# LCD_Interface.net
KiCad netlist of a schematic drawn in Altium Designer
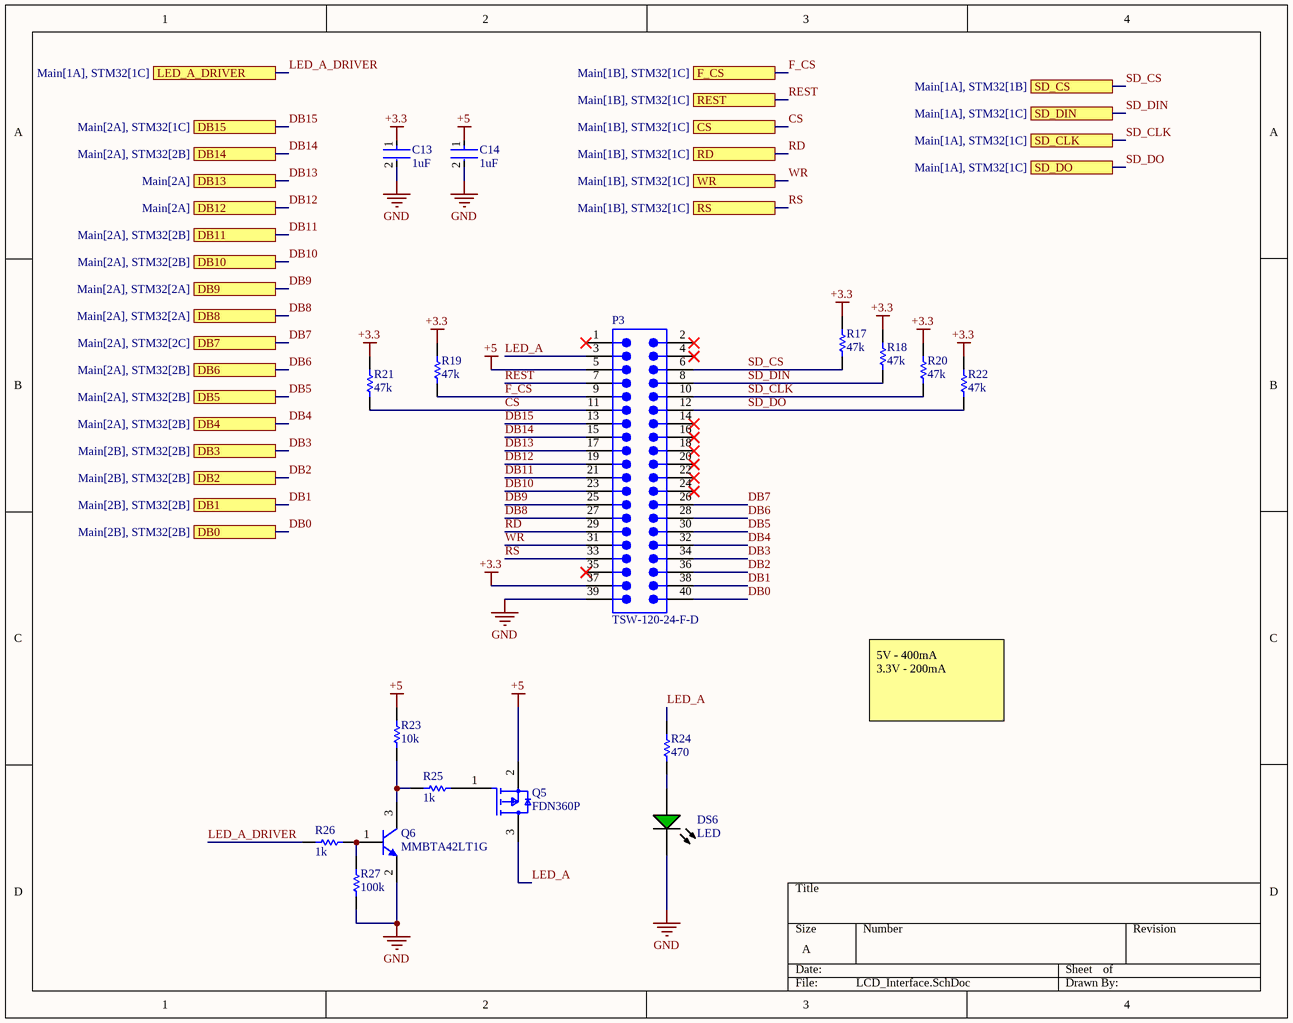
[diagram p0: LCD_Interface.SchDoc]

(export (version "E")
  (design (tool "Eeschema 10.0.6"))
  (components
    (comp (ref "C13")
      (value "1uF")
      (footprint "FP-0805-L_2_01_0_2-W_1_25-IPC_B")
      (description "General Purpose Ceramic Capacitor, 0805, 100nF, 10%, X7R, 15%, 100V")
      (fields (field (name "VOLTAGE") "100V") (field (name "TOLERANCE") "10%"))
      (libsource (lib "Altium Content Vault") (part "b4654b650e69147ec39a6b967a45e02"))
    )
    (comp (ref "C14")
      (value "1uF")
      (footprint "FP-0805-L_2_01_0_2-W_1_25-IPC_B")
      (description "General Purpose Ceramic Capacitor, 0805, 100nF, 10%, X7R, 15%, 100V")
      (fields (field (name "VOLTAGE") "100V") (field (name "TOLERANCE") "10%"))
      (libsource (lib "Altium Content Vault") (part "b4654b650e69147ec39a6b967a45e02"))
    )
    (comp (ref "DS6")
      (value "LED")
      (footprint "AVAG-HSMX-C170_V")
      (description "Chip LED, Green, 2.2 V, -40 to 85 degC, 2-Pin SMD, Pb-Free, Tape and Reel")
      (fields (field (name "MANUFACTURER") "Avago"))
      (libsource (lib "Altium Content Vault") (part "LED_GREEN_A1K2-2"))
    )
    (comp (ref "P3")
      (value "TSW-120-24-F-D")
      (footprint "SMTC-TSW-120-24-X-D")
      (description "0.025\" SQ Post Header, Through-hole, Vertical, -55 to 125 degC, 2.54 mm Pitch, 40-Pin, Male, RoHS")
      (fields (field (name "MANUFACTURER") "Samtec"))
      (libsource (lib "Altium Content Vault") (part "SMTC-TSW-120-X-X-D-X"))
    )
    (comp (ref "Q5")
      (value "FDN360P")
      (footprint "FP-527AG-IPC_B")
      (description "MOSFET P-CH 30V 2A SSOT3")
      (libsource (lib "Altium Content Vault") (part "d96140c8e79ef71348df71fb49a9466"))
    )
    (comp (ref "Q6")
      (value "MMBTA42LT1G")
      (footprint "ONSC-SOT-23-3-318-08_V")
      (description "High Voltage Transistor, NPN Silicon, 3-Pin SOT-23, Pb-Free, Tape and Reel")
      (fields (field (name "MANUFACTURER") "On Semiconductor"))
      (libsource (lib "Altium Content Vault") (part "ONSC-NPN-B1E2C3-3"))
    )
    (comp (ref "R17")
      (value "47k")
      (footprint "RESC2013X50X30LL20T20")
      (fields (field (name "MANUFACTURER") "Vishay Dale") (field (name "PART NUMBER") "CRCW08050000Z0EA"))
      (libsource (lib "Altium Content Vault") (part "RES"))
    )
    (comp (ref "R18")
      (value "47k")
      (footprint "RESC2013X50X30LL20T20")
      (fields (field (name "MANUFACTURER") "Vishay Dale") (field (name "PART NUMBER") "CRCW08050000Z0EA"))
      (libsource (lib "Altium Content Vault") (part "RES"))
    )
    (comp (ref "R19")
      (value "47k")
      (footprint "RESC2013X50X30LL20T20")
      (fields (field (name "MANUFACTURER") "Vishay Dale") (field (name "PART NUMBER") "CRCW08050000Z0EA"))
      (libsource (lib "Altium Content Vault") (part "RES"))
    )
    (comp (ref "R20")
      (value "47k")
      (footprint "RESC2013X50X30LL20T20")
      (fields (field (name "MANUFACTURER") "Vishay Dale") (field (name "PART NUMBER") "CRCW08050000Z0EA"))
      (libsource (lib "Altium Content Vault") (part "RES"))
    )
    (comp (ref "R21")
      (value "47k")
      (footprint "RESC2013X50X30LL20T20")
      (fields (field (name "MANUFACTURER") "Vishay Dale") (field (name "PART NUMBER") "CRCW08050000Z0EA"))
      (libsource (lib "Altium Content Vault") (part "RES"))
    )
    (comp (ref "R22")
      (value "47k")
      (footprint "RESC2013X50X30LL20T20")
      (fields (field (name "MANUFACTURER") "Vishay Dale") (field (name "PART NUMBER") "CRCW08050000Z0EA"))
      (libsource (lib "Altium Content Vault") (part "RES"))
    )
    (comp (ref "R23")
      (value "10k")
      (footprint "RESC2013X50X30LL20T20")
      (fields (field (name "MANUFACTURER") "Vishay Dale") (field (name "PART NUMBER") "CRCW08050000Z0EA"))
      (libsource (lib "Altium Content Vault") (part "RES"))
    )
    (comp (ref "R24")
      (value "470")
      (footprint "RESC2013X50X30LL20T20")
      (fields (field (name "MANUFACTURER") "Vishay Dale") (field (name "PART NUMBER") "CRCW08050000Z0EA"))
      (libsource (lib "Altium Content Vault") (part "RES"))
    )
    (comp (ref "R25")
      (value "1k")
      (footprint "RESC2013X50X30LL20T20")
      (fields (field (name "MANUFACTURER") "Vishay Dale") (field (name "PART NUMBER") "CRCW08050000Z0EA"))
      (libsource (lib "Altium Content Vault") (part "RES"))
    )
    (comp (ref "R26")
      (value "1k")
      (footprint "RESC2013X50X30LL20T20")
      (fields (field (name "MANUFACTURER") "Vishay Dale") (field (name "PART NUMBER") "CRCW08050000Z0EA"))
      (libsource (lib "Altium Content Vault") (part "RES"))
    )
    (comp (ref "R27")
      (value "100k")
      (footprint "RESC2013X50X30LL20T20")
      (fields (field (name "MANUFACTURER") "Vishay Dale") (field (name "PART NUMBER") "CRCW08050000Z0EA"))
      (libsource (lib "Altium Content Vault") (part "RES"))
    )
  )
  (nets
    (net (code "1") (name "+3.3") (class "Default")
      (node (ref "C13") (pin "1") (pinfunction "1_1") (pintype "passive"))
      (node (ref "P3") (pin "37") (pinfunction "37_37") (pintype "passive"))
      (node (ref "R17") (pin "2") (pinfunction "2_2") (pintype "passive"))
      (node (ref "R18") (pin "2") (pinfunction "2_2") (pintype "passive"))
      (node (ref "R19") (pin "2") (pinfunction "2_2") (pintype "passive"))
      (node (ref "R20") (pin "2") (pinfunction "2_2") (pintype "passive"))
      (node (ref "R21") (pin "2") (pinfunction "2_2") (pintype "passive"))
      (node (ref "R22") (pin "2") (pinfunction "2_2") (pintype "passive"))
    )
    (net (code "2") (name "+5") (class "Default")
      (node (ref "C14") (pin "1") (pinfunction "1_1") (pintype "passive"))
      (node (ref "P3") (pin "5") (pinfunction "5_5") (pintype "passive"))
      (node (ref "Q5") (pin "2") (pinfunction "S_2") (pintype "passive"))
      (node (ref "R23") (pin "2") (pinfunction "2_2") (pintype "passive"))
    )
    (net (code "4") (name "/CS") (class "Default")
      (node (ref "P3") (pin "11") (pinfunction "11_11") (pintype "passive"))
      (node (ref "R21") (pin "1") (pinfunction "1_1") (pintype "passive"))
    )
    (net (code "5") (name "/DB0") (class "Default")
      (node (ref "P3") (pin "40") (pinfunction "40_40") (pintype "passive"))
    )
    (net (code "6") (name "/DB1") (class "Default")
      (node (ref "P3") (pin "38") (pinfunction "38_38") (pintype "passive"))
    )
    (net (code "7") (name "/DB2") (class "Default")
      (node (ref "P3") (pin "36") (pinfunction "36_36") (pintype "passive"))
    )
    (net (code "8") (name "/DB3") (class "Default")
      (node (ref "P3") (pin "34") (pinfunction "34_34") (pintype "passive"))
    )
    (net (code "9") (name "/DB4") (class "Default")
      (node (ref "P3") (pin "32") (pinfunction "32_32") (pintype "passive"))
    )
    (net (code "10") (name "/DB5") (class "Default")
      (node (ref "P3") (pin "30") (pinfunction "30_30") (pintype "passive"))
    )
    (net (code "11") (name "/DB6") (class "Default")
      (node (ref "P3") (pin "28") (pinfunction "28_28") (pintype "passive"))
    )
    (net (code "12") (name "/DB7") (class "Default")
      (node (ref "P3") (pin "26") (pinfunction "26_26") (pintype "passive"))
    )
    (net (code "13") (name "/DB8") (class "Default")
      (node (ref "P3") (pin "27") (pinfunction "27_27") (pintype "passive"))
    )
    (net (code "14") (name "/DB9") (class "Default")
      (node (ref "P3") (pin "25") (pinfunction "25_25") (pintype "passive"))
    )
    (net (code "15") (name "/DB10") (class "Default")
      (node (ref "P3") (pin "23") (pinfunction "23_23") (pintype "passive"))
    )
    (net (code "16") (name "/DB11") (class "Default")
      (node (ref "P3") (pin "21") (pinfunction "21_21") (pintype "passive"))
    )
    (net (code "17") (name "/DB12") (class "Default")
      (node (ref "P3") (pin "19") (pinfunction "19_19") (pintype "passive"))
    )
    (net (code "18") (name "/DB13") (class "Default")
      (node (ref "P3") (pin "17") (pinfunction "17_17") (pintype "passive"))
    )
    (net (code "19") (name "/DB14") (class "Default")
      (node (ref "P3") (pin "15") (pinfunction "15_15") (pintype "passive"))
    )
    (net (code "20") (name "/DB15") (class "Default")
      (node (ref "P3") (pin "13") (pinfunction "13_13") (pintype "passive"))
    )
    (net (code "21") (name "/F_CS") (class "Default")
      (node (ref "P3") (pin "9") (pinfunction "9_9") (pintype "passive"))
      (node (ref "R19") (pin "1") (pinfunction "1_1") (pintype "passive"))
    )
    (net (code "22") (name "/LED_A") (class "Default")
      (node (ref "P3") (pin "3") (pinfunction "3_3") (pintype "passive"))
      (node (ref "Q5") (pin "3") (pinfunction "D_3") (pintype "passive"))
      (node (ref "R24") (pin "2") (pinfunction "2_2") (pintype "passive"))
    )
    (net (code "23") (name "/LED_A_DRIVER") (class "Default")
      (node (ref "R26") (pin "1") (pinfunction "1_1") (pintype "passive"))
    )
    (net (code "24") (name "/RD") (class "Default")
      (node (ref "P3") (pin "29") (pinfunction "29_29") (pintype "passive"))
    )
    (net (code "25") (name "/REST") (class "Default")
      (node (ref "P3") (pin "7") (pinfunction "7_7") (pintype "passive"))
    )
    (net (code "26") (name "/RS") (class "Default")
      (node (ref "P3") (pin "33") (pinfunction "33_33") (pintype "passive"))
    )
    (net (code "27") (name "/SD_CLK") (class "Default")
      (node (ref "P3") (pin "10") (pinfunction "10_10") (pintype "passive"))
      (node (ref "R20") (pin "1") (pinfunction "1_1") (pintype "passive"))
    )
    (net (code "28") (name "/SD_CS") (class "Default")
      (node (ref "P3") (pin "6") (pinfunction "6_6") (pintype "passive"))
      (node (ref "R17") (pin "1") (pinfunction "1_1") (pintype "passive"))
    )
    (net (code "29") (name "/SD_DIN") (class "Default")
      (node (ref "P3") (pin "8") (pinfunction "8_8") (pintype "passive"))
      (node (ref "R18") (pin "1") (pinfunction "1_1") (pintype "passive"))
    )
    (net (code "30") (name "/SD_DO") (class "Default")
      (node (ref "P3") (pin "12") (pinfunction "12_12") (pintype "passive"))
      (node (ref "R22") (pin "1") (pinfunction "1_1") (pintype "passive"))
    )
    (net (code "31") (name "/WR") (class "Default")
      (node (ref "P3") (pin "31") (pinfunction "31_31") (pintype "passive"))
    )
    (net (code "32") (name "GND") (class "Default")
      (node (ref "C13") (pin "2") (pinfunction "2_2") (pintype "passive"))
      (node (ref "C14") (pin "2") (pinfunction "2_2") (pintype "passive"))
      (node (ref "DS6") (pin "2") (pinfunction "K_2") (pintype "passive"))
      (node (ref "P3") (pin "39") (pinfunction "39_39") (pintype "passive"))
      (node (ref "Q6") (pin "2") (pinfunction "E_2") (pintype "passive"))
      (node (ref "R27") (pin "1") (pinfunction "1_1") (pintype "passive"))
    )
    (net (code "33") (name "Net-(DS6-A)") (class "Default")
      (node (ref "DS6") (pin "1") (pinfunction "A_1") (pintype "passive"))
      (node (ref "R24") (pin "1") (pinfunction "1_1") (pintype "passive"))
    )
    (net (code "34") (name "Net-(Q5-G)") (class "Default")
      (node (ref "Q5") (pin "1") (pinfunction "G_1") (pintype "passive"))
      (node (ref "R25") (pin "2") (pinfunction "2_2") (pintype "passive"))
    )
    (net (code "35") (name "Net-(Q6-B)") (class "Default")
      (node (ref "Q6") (pin "1") (pinfunction "B_1") (pintype "passive"))
      (node (ref "R26") (pin "2") (pinfunction "2_2") (pintype "passive"))
      (node (ref "R27") (pin "2") (pinfunction "2_2") (pintype "passive"))
    )
    (net (code "36") (name "Net-(Q6-C)") (class "Default")
      (node (ref "Q6") (pin "3") (pinfunction "C_3") (pintype "passive"))
      (node (ref "R23") (pin "1") (pinfunction "1_1") (pintype "passive"))
      (node (ref "R25") (pin "1") (pinfunction "1_1") (pintype "passive"))
    )
    (net (code "37") (name "unconnected-(P3-Pad1)") (class "Default")
      (node (ref "P3") (pin "1") (pinfunction "1_1") (pintype "passive+no_connect"))
    )
    (net (code "38") (name "unconnected-(P3-Pad2)") (class "Default")
      (node (ref "P3") (pin "2") (pinfunction "2_2") (pintype "passive+no_connect"))
    )
    (net (code "39") (name "unconnected-(P3-Pad4)") (class "Default")
      (node (ref "P3") (pin "4") (pinfunction "4_4") (pintype "passive+no_connect"))
    )
    (net (code "40") (name "unconnected-(P3-Pad14)") (class "Default")
      (node (ref "P3") (pin "14") (pinfunction "14_14") (pintype "passive+no_connect"))
    )
    (net (code "41") (name "unconnected-(P3-Pad16)") (class "Default")
      (node (ref "P3") (pin "16") (pinfunction "16_16") (pintype "passive+no_connect"))
    )
    (net (code "42") (name "unconnected-(P3-Pad18)") (class "Default")
      (node (ref "P3") (pin "18") (pinfunction "18_18") (pintype "passive+no_connect"))
    )
    (net (code "43") (name "unconnected-(P3-Pad20)") (class "Default")
      (node (ref "P3") (pin "20") (pinfunction "20_20") (pintype "passive+no_connect"))
    )
    (net (code "44") (name "unconnected-(P3-Pad22)") (class "Default")
      (node (ref "P3") (pin "22") (pinfunction "22_22") (pintype "passive+no_connect"))
    )
    (net (code "45") (name "unconnected-(P3-Pad24)") (class "Default")
      (node (ref "P3") (pin "24") (pinfunction "24_24") (pintype "passive+no_connect"))
    )
    (net (code "46") (name "unconnected-(P3-Pad35)") (class "Default")
      (node (ref "P3") (pin "35") (pinfunction "35_35") (pintype "passive+no_connect"))
    )
  )
)
